# WH-MDC05F3E5_comm_v3_0.net
KiCad netlist of a schematic drawn in EAGLE
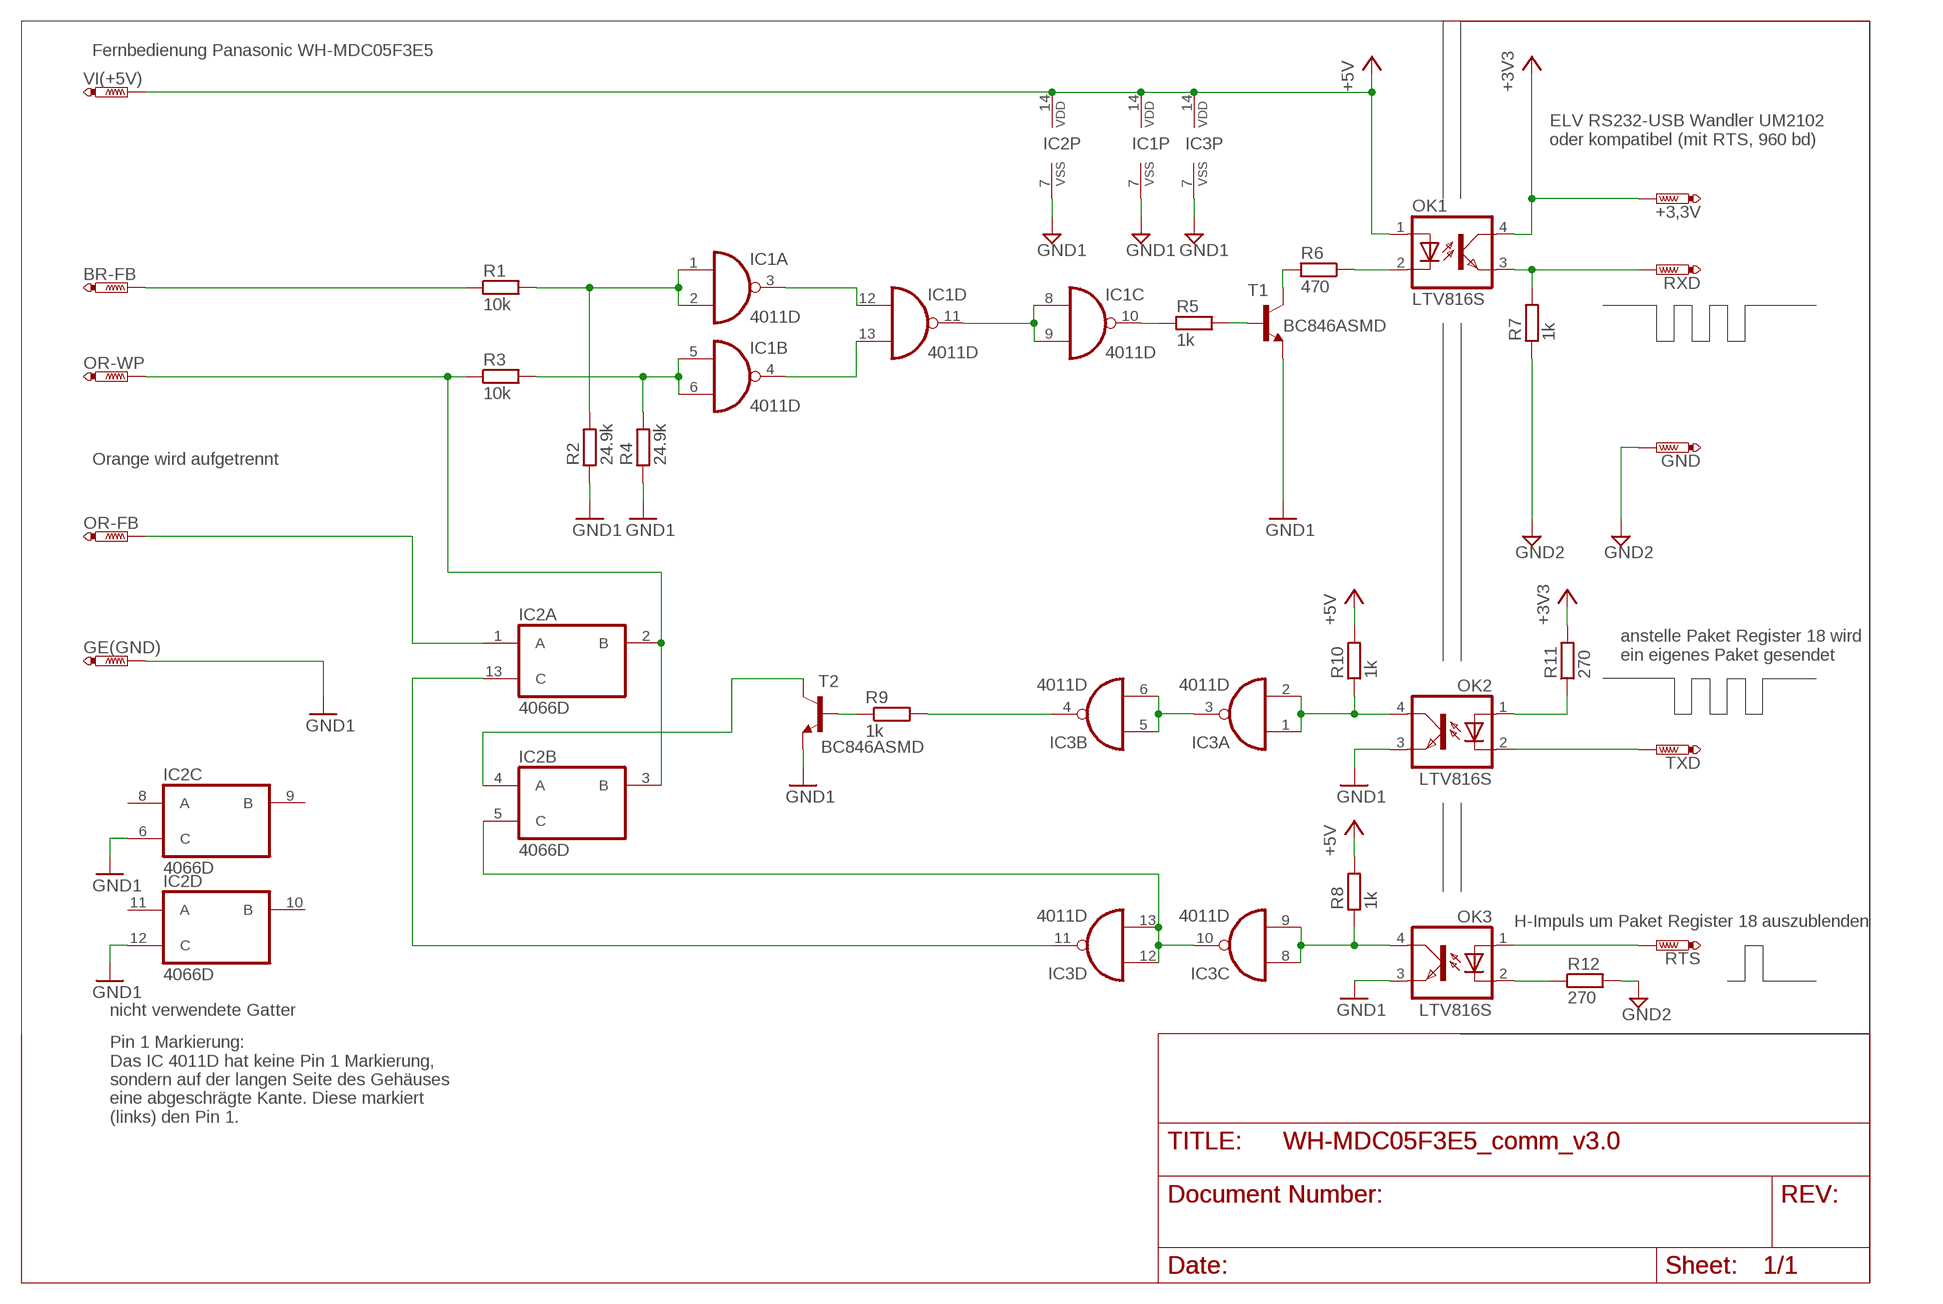
[diagram p0: schematic, sheet 1]

(export (version "E")
  (design (tool "Eeschema 10.0.6"))
  (components
    (comp (ref "+3,3V")
      (value "PTR1PAD1-17")
      (footprint "eagle-import:P1-17")
      (libsource (lib "eagle-import") (part "PTR1PAD1-17"))
    )
    (comp (ref "BR-FB")
      (value "PTR1PAD1-17")
      (footprint "eagle-import:P1-17")
      (libsource (lib "eagle-import") (part "PTR1PAD1-17"))
    )
    (comp (ref "GE(GND)")
      (value "PTR1PAD1-17")
      (footprint "eagle-import:P1-17")
      (libsource (lib "eagle-import") (part "PTR1PAD1-17"))
    )
    (comp (ref "GND")
      (value "PTR1PAD1-17")
      (footprint "eagle-import:P1-17")
      (libsource (lib "eagle-import") (part "PTR1PAD1-17"))
    )
    (comp (ref "IC1")
      (value "4011D")
      (footprint "eagle-import:SO14")
      (libsource (lib "eagle-import") (part "4011D"))
    )
    (comp (ref "IC2")
      (value "4066D")
      (footprint "eagle-import:SO14")
      (libsource (lib "eagle-import") (part "4066D"))
    )
    (comp (ref "IC3")
      (value "4011D")
      (footprint "eagle-import:SO14")
      (libsource (lib "eagle-import") (part "4011D"))
    )
    (comp (ref "OK1")
      (value "LTV816S")
      (footprint "eagle-import:SMD4")
      (libsource (lib "eagle-import") (part "LTV816S"))
    )
    (comp (ref "OK2")
      (value "LTV816S")
      (footprint "eagle-import:SMD4")
      (libsource (lib "eagle-import") (part "LTV816S"))
    )
    (comp (ref "OK3")
      (value "LTV816S")
      (footprint "eagle-import:SMD4")
      (libsource (lib "eagle-import") (part "LTV816S"))
    )
    (comp (ref "OR-FB")
      (value "PTR1PAD1-17")
      (footprint "eagle-import:P1-17")
      (libsource (lib "eagle-import") (part "PTR1PAD1-17"))
    )
    (comp (ref "OR-WP")
      (value "PTR1PAD1-17")
      (footprint "eagle-import:P1-17")
      (libsource (lib "eagle-import") (part "PTR1PAD1-17"))
    )
    (comp (ref "R1")
      (value "10k")
      (footprint "eagle-import:R0805")
      (libsource (lib "eagle-import") (part "R-EU_R0805"))
    )
    (comp (ref "R2")
      (value "24.9k")
      (footprint "eagle-import:R0805")
      (libsource (lib "eagle-import") (part "R-EU_R0805"))
    )
    (comp (ref "R3")
      (value "10k")
      (footprint "eagle-import:R0805")
      (libsource (lib "eagle-import") (part "R-EU_R0805"))
    )
    (comp (ref "R4")
      (value "24.9k")
      (footprint "eagle-import:R0805")
      (libsource (lib "eagle-import") (part "R-EU_R0805"))
    )
    (comp (ref "R5")
      (value "1k")
      (footprint "eagle-import:R0805")
      (libsource (lib "eagle-import") (part "R-EU_R0805"))
    )
    (comp (ref "R6")
      (value "470")
      (footprint "eagle-import:R0805")
      (libsource (lib "eagle-import") (part "R-EU_R0805"))
    )
    (comp (ref "R7")
      (value "1k")
      (footprint "eagle-import:R0805")
      (libsource (lib "eagle-import") (part "R-EU_R0805"))
    )
    (comp (ref "R8")
      (value "1k")
      (footprint "eagle-import:R0805")
      (libsource (lib "eagle-import") (part "R-EU_R0805"))
    )
    (comp (ref "R9")
      (value "1k")
      (footprint "eagle-import:R0805")
      (libsource (lib "eagle-import") (part "R-EU_R0805"))
    )
    (comp (ref "R10")
      (value "1k")
      (footprint "eagle-import:R0805")
      (libsource (lib "eagle-import") (part "R-EU_R0805"))
    )
    (comp (ref "R11")
      (value "270")
      (footprint "eagle-import:R0805")
      (libsource (lib "eagle-import") (part "R-EU_R0805"))
    )
    (comp (ref "R12")
      (value "270")
      (footprint "eagle-import:R0805")
      (libsource (lib "eagle-import") (part "R-EU_R0805"))
    )
    (comp (ref "RTS")
      (value "PTR1PAD1-17")
      (footprint "eagle-import:P1-17")
      (libsource (lib "eagle-import") (part "PTR1PAD1-17"))
    )
    (comp (ref "RXD")
      (value "PTR1PAD1-17")
      (footprint "eagle-import:P1-17")
      (libsource (lib "eagle-import") (part "PTR1PAD1-17"))
    )
    (comp (ref "T1")
      (value "BC846ASMD")
      (footprint "eagle-import:SOT23")
      (libsource (lib "eagle-import") (part "BC846SMDA"))
    )
    (comp (ref "T2")
      (value "BC846ASMD")
      (footprint "eagle-import:SOT23")
      (libsource (lib "eagle-import") (part "BC846SMDA"))
    )
    (comp (ref "TXD")
      (value "PTR1PAD1-17")
      (footprint "eagle-import:P1-17")
      (libsource (lib "eagle-import") (part "PTR1PAD1-17"))
    )
    (comp (ref "VI(+5V)")
      (value "PTR1PAD1-17")
      (footprint "eagle-import:P1-17")
      (libsource (lib "eagle-import") (part "PTR1PAD1-17"))
    )
  )
  (nets
    (net (code "1") (name "+3V3") (class "Default")
      (node (ref "+3,3V") (pin "TP") (pinfunction "TP_TP") (pintype "input"))
      (node (ref "OK1") (pin "4") (pinfunction "COL_4") (pintype "passive"))
      (node (ref "R11") (pin "2") (pinfunction "2_2") (pintype "passive"))
    )
    (net (code "2") (name "+5V") (class "Default")
      (node (ref "IC1") (pin "14") (pinfunction "VDD_14") (pintype "power_in"))
      (node (ref "IC2") (pin "14") (pinfunction "VDD_14") (pintype "power_in"))
      (node (ref "IC3") (pin "14") (pinfunction "VDD_14") (pintype "power_in"))
      (node (ref "OK1") (pin "1") (pinfunction "A_1") (pintype "passive"))
      (node (ref "R10") (pin "2") (pinfunction "2_2") (pintype "passive"))
      (node (ref "R8") (pin "2") (pinfunction "2_2") (pintype "passive"))
      (node (ref "VI(+5V)") (pin "TP") (pinfunction "TP_TP") (pintype "input"))
    )
    (net (code "3") (name "GND1") (class "Default")
      (node (ref "GE(GND)") (pin "TP") (pinfunction "TP_TP") (pintype "input"))
      (node (ref "IC1") (pin "7") (pinfunction "VSS_7") (pintype "power_in"))
      (node (ref "IC2") (pin "12") (pinfunction "C_12") (pintype "input"))
      (node (ref "IC2") (pin "6") (pinfunction "C_6") (pintype "input"))
      (node (ref "IC2") (pin "7") (pinfunction "VSS_7") (pintype "power_in"))
      (node (ref "IC3") (pin "7") (pinfunction "VSS_7") (pintype "power_in"))
      (node (ref "OK2") (pin "3") (pinfunction "EMIT_3") (pintype "passive"))
      (node (ref "OK3") (pin "3") (pinfunction "EMIT_3") (pintype "passive"))
      (node (ref "R2") (pin "1") (pinfunction "1_1") (pintype "passive"))
      (node (ref "R4") (pin "1") (pinfunction "1_1") (pintype "passive"))
      (node (ref "T1") (pin "2") (pinfunction "E_2") (pintype "passive"))
      (node (ref "T2") (pin "2") (pinfunction "E_2") (pintype "passive"))
    )
    (net (code "4") (name "GND2") (class "Default")
      (node (ref "GND") (pin "TP") (pinfunction "TP_TP") (pintype "input"))
      (node (ref "R12") (pin "2") (pinfunction "2_2") (pintype "passive"))
      (node (ref "R7") (pin "1") (pinfunction "1_1") (pintype "passive"))
    )
    (net (code "5") (name "Net-(BR-FB-PadTP)") (class "Default")
      (node (ref "BR-FB") (pin "TP") (pinfunction "TP_TP") (pintype "input"))
      (node (ref "R1") (pin "1") (pinfunction "1_1") (pintype "passive"))
    )
    (net (code "6") (name "Net-(IC1A-I0)") (class "Default")
      (node (ref "IC1") (pin "1") (pinfunction "I0_1") (pintype "input"))
      (node (ref "IC1") (pin "2") (pinfunction "I1_2") (pintype "input"))
      (node (ref "R1") (pin "2") (pinfunction "2_2") (pintype "passive"))
      (node (ref "R2") (pin "2") (pinfunction "2_2") (pintype "passive"))
    )
    (net (code "7") (name "Net-(IC1A-O)") (class "Default")
      (node (ref "IC1") (pin "12") (pinfunction "I0_12") (pintype "input"))
      (node (ref "IC1") (pin "3") (pinfunction "O_3") (pintype "output"))
    )
    (net (code "8") (name "Net-(IC1B-I0)") (class "Default")
      (node (ref "IC1") (pin "5") (pinfunction "I0_5") (pintype "input"))
      (node (ref "IC1") (pin "6") (pinfunction "I1_6") (pintype "input"))
      (node (ref "R3") (pin "2") (pinfunction "2_2") (pintype "passive"))
      (node (ref "R4") (pin "2") (pinfunction "2_2") (pintype "passive"))
    )
    (net (code "9") (name "Net-(IC1B-O)") (class "Default")
      (node (ref "IC1") (pin "13") (pinfunction "I1_13") (pintype "input"))
      (node (ref "IC1") (pin "4") (pinfunction "O_4") (pintype "output"))
    )
    (net (code "10") (name "Net-(IC1C-I0)") (class "Default")
      (node (ref "IC1") (pin "11") (pinfunction "O_11") (pintype "output"))
      (node (ref "IC1") (pin "8") (pinfunction "I0_8") (pintype "input"))
      (node (ref "IC1") (pin "9") (pinfunction "I1_9") (pintype "input"))
    )
    (net (code "11") (name "Net-(IC1C-O)") (class "Default")
      (node (ref "IC1") (pin "10") (pinfunction "O_10") (pintype "output"))
      (node (ref "R5") (pin "1") (pinfunction "1_1") (pintype "passive"))
    )
    (net (code "12") (name "Net-(IC2A-A)") (class "Default")
      (node (ref "IC2") (pin "1") (pinfunction "A_1") (pintype "tri_state"))
      (node (ref "OR-FB") (pin "TP") (pinfunction "TP_TP") (pintype "input"))
    )
    (net (code "13") (name "Net-(IC2A-B)") (class "Default")
      (node (ref "IC2") (pin "2") (pinfunction "B_2") (pintype "tri_state"))
      (node (ref "IC2") (pin "3") (pinfunction "B_3") (pintype "tri_state"))
      (node (ref "OR-WP") (pin "TP") (pinfunction "TP_TP") (pintype "input"))
      (node (ref "R3") (pin "1") (pinfunction "1_1") (pintype "passive"))
    )
    (net (code "14") (name "Net-(IC2A-C)") (class "Default")
      (node (ref "IC2") (pin "13") (pinfunction "C_13") (pintype "input"))
      (node (ref "IC3") (pin "11") (pinfunction "O_11") (pintype "output"))
    )
    (net (code "15") (name "Net-(IC2B-A)") (class "Default")
      (node (ref "IC2") (pin "4") (pinfunction "A_4") (pintype "tri_state"))
      (node (ref "T2") (pin "3") (pinfunction "C_3") (pintype "passive"))
    )
    (net (code "16") (name "Net-(IC2B-C)") (class "Default")
      (node (ref "IC2") (pin "5") (pinfunction "C_5") (pintype "input"))
      (node (ref "IC3") (pin "10") (pinfunction "O_10") (pintype "output"))
      (node (ref "IC3") (pin "12") (pinfunction "I0_12") (pintype "input"))
      (node (ref "IC3") (pin "13") (pinfunction "I1_13") (pintype "input"))
    )
    (net (code "17") (name "Net-(IC3A-I0)") (class "Default")
      (node (ref "IC3") (pin "1") (pinfunction "I0_1") (pintype "input"))
      (node (ref "IC3") (pin "2") (pinfunction "I1_2") (pintype "input"))
      (node (ref "OK2") (pin "4") (pinfunction "COL_4") (pintype "passive"))
      (node (ref "R10") (pin "1") (pinfunction "1_1") (pintype "passive"))
    )
    (net (code "18") (name "Net-(IC3A-O)") (class "Default")
      (node (ref "IC3") (pin "3") (pinfunction "O_3") (pintype "output"))
      (node (ref "IC3") (pin "5") (pinfunction "I0_5") (pintype "input"))
      (node (ref "IC3") (pin "6") (pinfunction "I1_6") (pintype "input"))
    )
    (net (code "19") (name "Net-(IC3B-O)") (class "Default")
      (node (ref "IC3") (pin "4") (pinfunction "O_4") (pintype "output"))
      (node (ref "R9") (pin "2") (pinfunction "2_2") (pintype "passive"))
    )
    (net (code "20") (name "Net-(IC3C-I0)") (class "Default")
      (node (ref "IC3") (pin "8") (pinfunction "I0_8") (pintype "input"))
      (node (ref "IC3") (pin "9") (pinfunction "I1_9") (pintype "input"))
      (node (ref "OK3") (pin "4") (pinfunction "COL_4") (pintype "passive"))
      (node (ref "R8") (pin "1") (pinfunction "1_1") (pintype "passive"))
    )
    (net (code "21") (name "Net-(OK1-C)") (class "Default")
      (node (ref "OK1") (pin "2") (pinfunction "C_2") (pintype "passive"))
      (node (ref "R6") (pin "1") (pinfunction "1_1") (pintype "passive"))
    )
    (net (code "22") (name "Net-(OK1-EMIT)") (class "Default")
      (node (ref "OK1") (pin "3") (pinfunction "EMIT_3") (pintype "passive"))
      (node (ref "R7") (pin "2") (pinfunction "2_2") (pintype "passive"))
      (node (ref "RXD") (pin "TP") (pinfunction "TP_TP") (pintype "input"))
    )
    (net (code "23") (name "Net-(OK2-A)") (class "Default")
      (node (ref "OK2") (pin "1") (pinfunction "A_1") (pintype "passive"))
      (node (ref "R11") (pin "1") (pinfunction "1_1") (pintype "passive"))
    )
    (net (code "24") (name "Net-(OK2-C)") (class "Default")
      (node (ref "OK2") (pin "2") (pinfunction "C_2") (pintype "passive"))
      (node (ref "TXD") (pin "TP") (pinfunction "TP_TP") (pintype "input"))
    )
    (net (code "25") (name "Net-(OK3-A)") (class "Default")
      (node (ref "OK3") (pin "1") (pinfunction "A_1") (pintype "passive"))
      (node (ref "RTS") (pin "TP") (pinfunction "TP_TP") (pintype "input"))
    )
    (net (code "26") (name "Net-(OK3-C)") (class "Default")
      (node (ref "OK3") (pin "2") (pinfunction "C_2") (pintype "passive"))
      (node (ref "R12") (pin "1") (pinfunction "1_1") (pintype "passive"))
    )
    (net (code "27") (name "Net-(T1-B)") (class "Default")
      (node (ref "R5") (pin "2") (pinfunction "2_2") (pintype "passive"))
      (node (ref "T1") (pin "1") (pinfunction "B_1") (pintype "passive"))
    )
    (net (code "28") (name "Net-(T1-C)") (class "Default")
      (node (ref "R6") (pin "2") (pinfunction "2_2") (pintype "passive"))
      (node (ref "T1") (pin "3") (pinfunction "C_3") (pintype "passive"))
    )
    (net (code "29") (name "Net-(T2-B)") (class "Default")
      (node (ref "R9") (pin "1") (pinfunction "1_1") (pintype "passive"))
      (node (ref "T2") (pin "1") (pinfunction "B_1") (pintype "passive"))
    )
    (net (code "30") (name "unconnected-(IC2C-A-Pad8)") (class "Default")
      (node (ref "IC2") (pin "8") (pinfunction "A_8") (pintype "tri_state"))
    )
    (net (code "31") (name "unconnected-(IC2C-B-Pad9)") (class "Default")
      (node (ref "IC2") (pin "9") (pinfunction "B_9") (pintype "tri_state"))
    )
    (net (code "32") (name "unconnected-(IC2D-A-Pad11)") (class "Default")
      (node (ref "IC2") (pin "11") (pinfunction "A_11") (pintype "tri_state"))
    )
    (net (code "33") (name "unconnected-(IC2D-B-Pad10)") (class "Default")
      (node (ref "IC2") (pin "10") (pinfunction "B_10") (pintype "tri_state"))
    )
  )
)
